# Camera_IR.net
KiCad netlist of a schematic drawn in EasyEDA
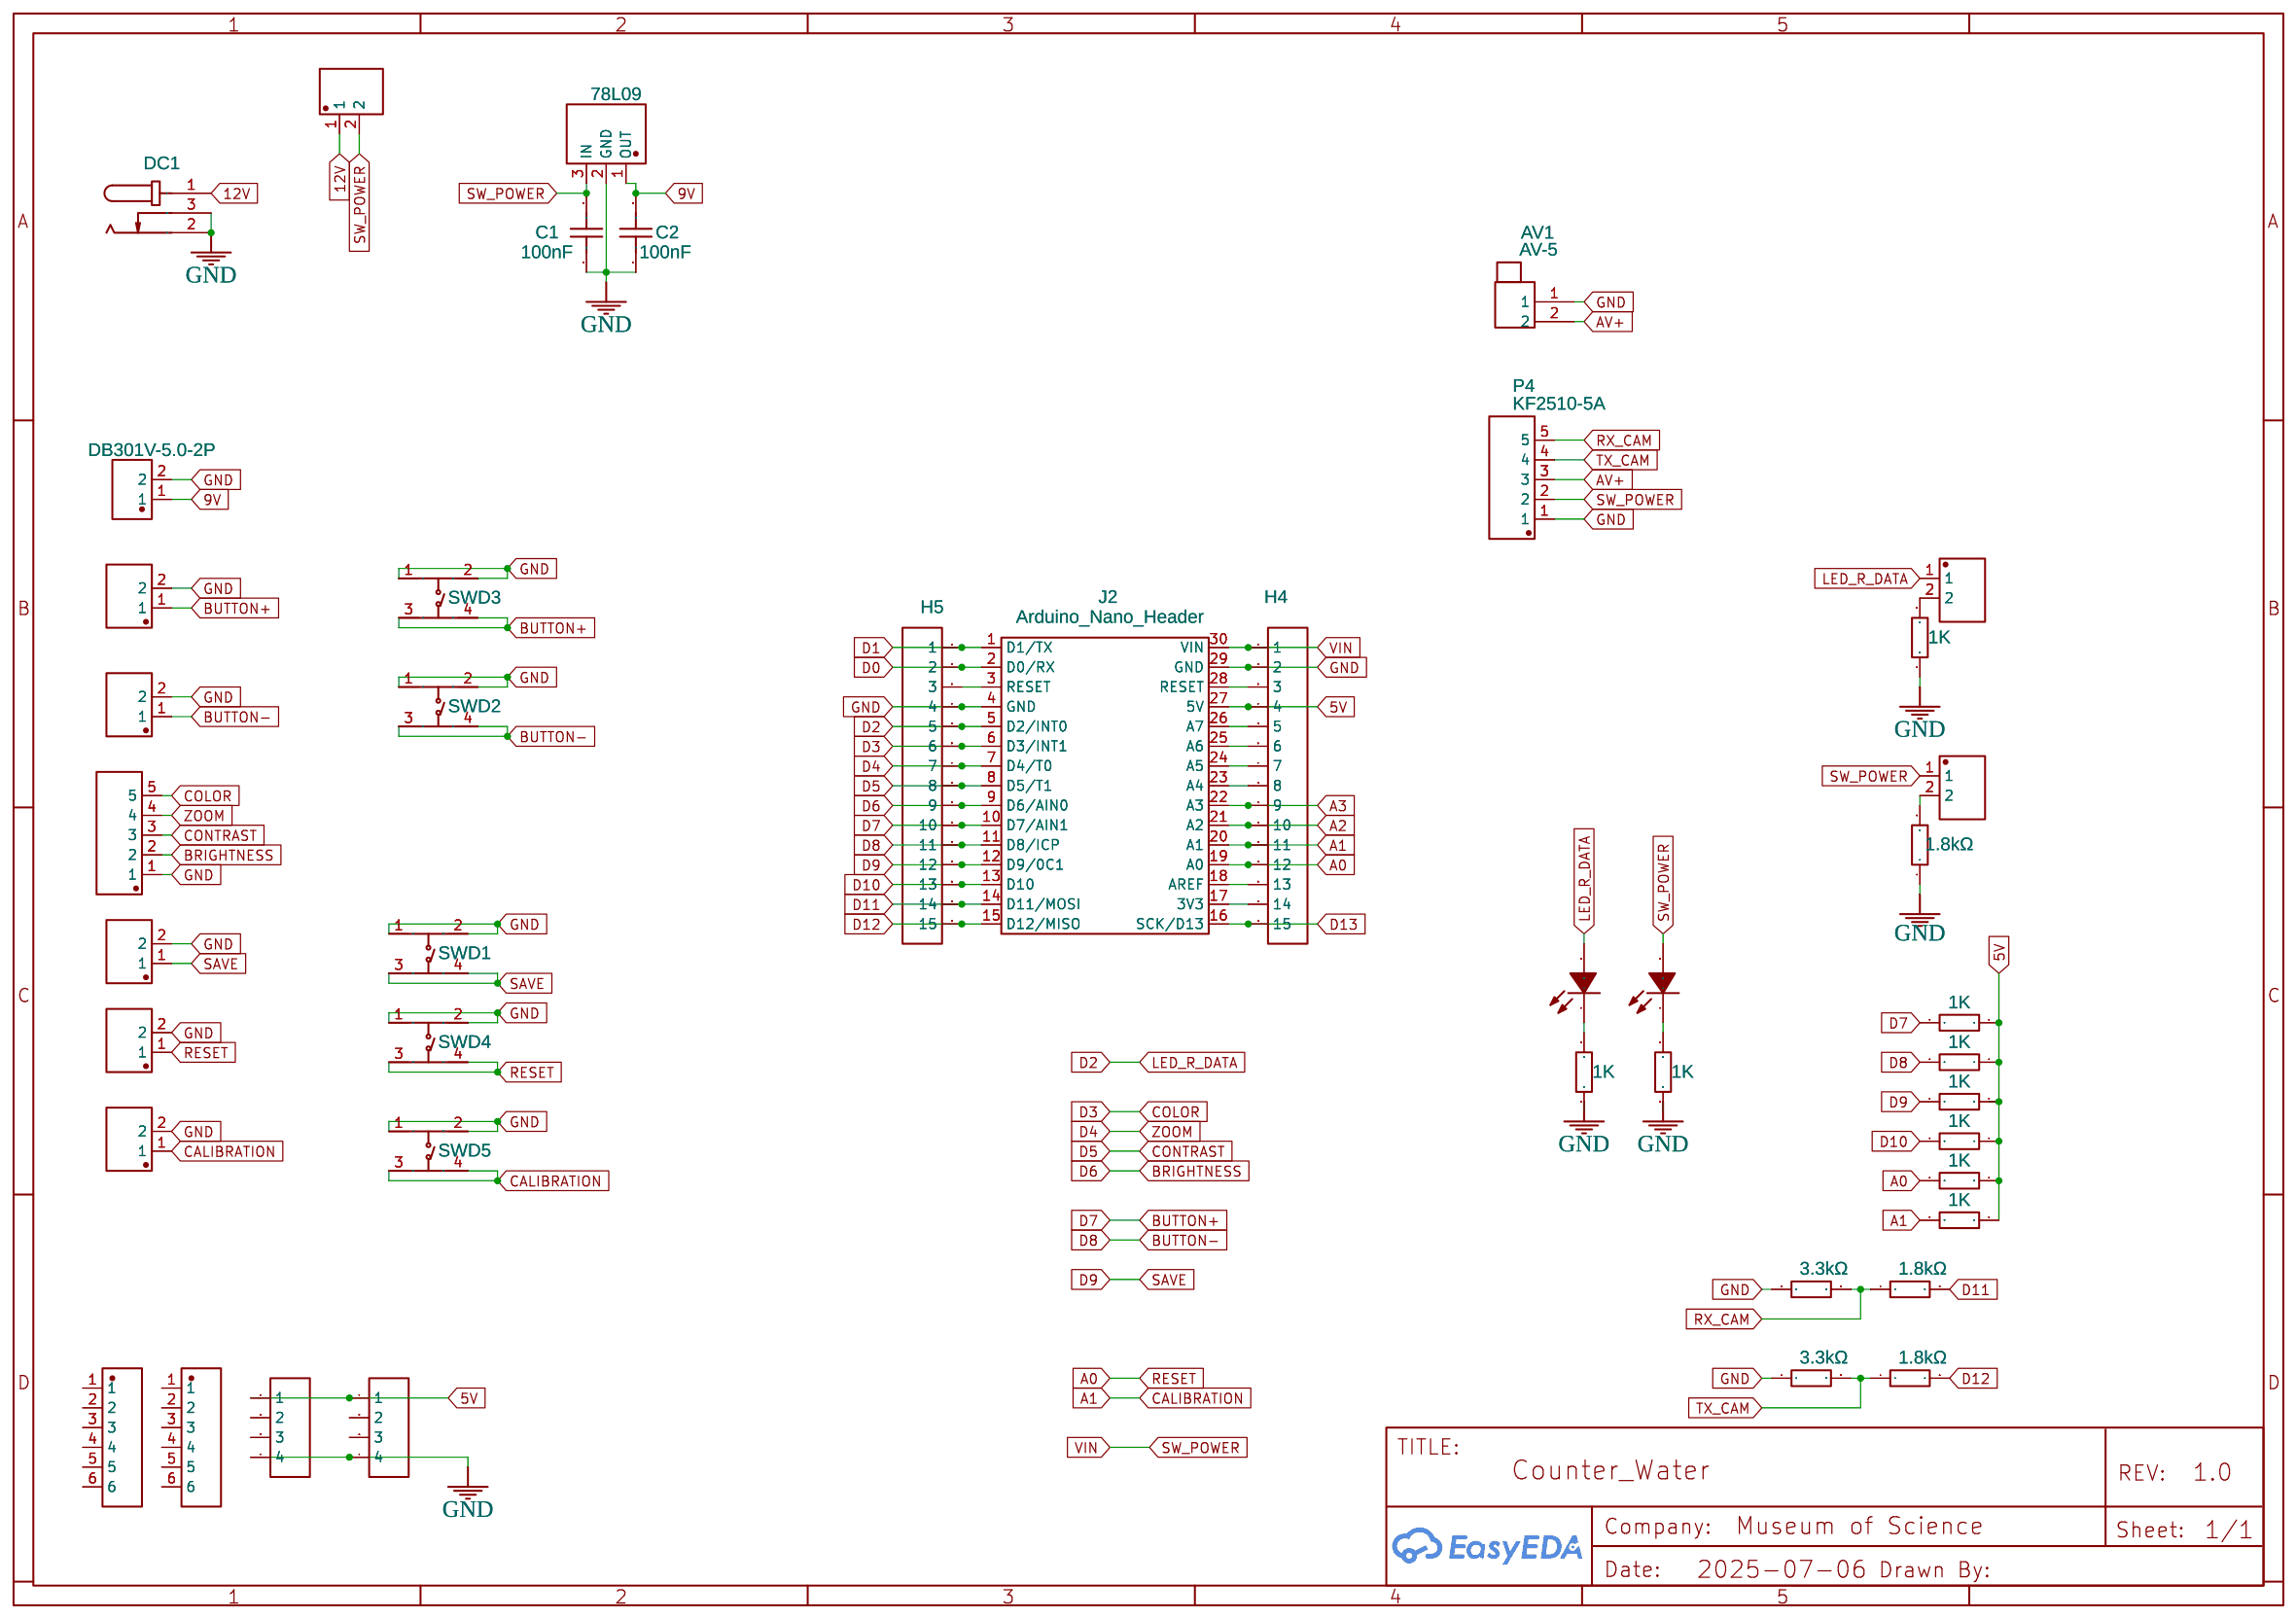
[diagram p0: schematic sheet]

(export (version "E")
  (design (tool "Eeschema 10.0.6"))
  (components
    (comp (ref "A0")
      (value "RESET")
      (fields (field (name "Manufacturer Part") "KF2510-2A") (field (name "Manufacturer") "BOOMELE"))
      (libsource (lib "") (part "KF2510-2A_1"))
    )
    (comp (ref "A1")
      (value "FFC")
      (fields (field (name "Manufacturer Part") "KF2510-2A") (field (name "Manufacturer") "BOOMELE"))
      (libsource (lib "") (part "KF2510-2A_1"))
    )
    (comp (ref "AV1")
      (value "AV-5")
      (fields (field (name "Manufacturer") "BOOMELE(博穆精密)"))
      (libsource (lib "") (part "AV-5"))
    )
    (comp (ref "C1")
      (value "100nF")
      (fields
        (field (name "Manufacturer Part") "CC0603KRX7R9BB104")
        (field (name "Manufacturer") "YAGEO(国巨)")
      )
      (libsource (lib "") (part "CC0603KRX7R9BB104"))
    )
    (comp (ref "C2")
      (value "100nF")
      (fields
        (field (name "Manufacturer Part") "CC0603KRX7R9BB104")
        (field (name "Manufacturer") "YAGEO(国巨)")
      )
      (libsource (lib "") (part "CC0603KRX7R9BB104"))
    )
    (comp (ref "D2")
      (value "LED")
      (fields (field (name "Manufacturer Part") "KF2510-2A") (field (name "Manufacturer") "BOOMELE"))
      (libsource (lib "") (part "KF2510-2A_3"))
    )
    (comp (ref "D7")
      (value "B+")
      (fields (field (name "Manufacturer Part") "KF2510-2A") (field (name "Manufacturer") "BOOMELE"))
      (libsource (lib "") (part "KF2510-2A"))
    )
    (comp (ref "D8")
      (value "B-")
      (fields (field (name "Manufacturer Part") "KF2510-2A") (field (name "Manufacturer") "BOOMELE"))
      (libsource (lib "") (part "KF2510-2A"))
    )
    (comp (ref "D9")
      (value "SAVE")
      (fields (field (name "Manufacturer Part") "KF2510-2A") (field (name "Manufacturer") "BOOMELE"))
      (libsource (lib "") (part "KF2510-2A"))
    )
    (comp (ref "DC1")
      (value "DC")
      (fields (field (name "Manufacturer Part") "DC005-2.0MM") (field (name "Manufacturer") "SOFNG"))
      (libsource (lib "") (part "DC005-2.0MM"))
    )
    (comp (ref "ERL1")
      (value "1K")
      (fields (field (name "Manufacturer Part") "0603WAF1001T5E") (field (name "Manufacturer") "UniOhm"))
      (libsource (lib "") (part "0603WAF1001T5E_1"))
    )
    (comp (ref "ERL2")
      (value "1K")
      (fields (field (name "Manufacturer Part") "0603WAF1001T5E") (field (name "Manufacturer") "UniOhm"))
      (libsource (lib "") (part "0603WAF1001T5E"))
    )
    (comp (ref "ERL3")
      (value "1K")
      (fields (field (name "Manufacturer Part") "0603WAF1001T5E") (field (name "Manufacturer") "UniOhm"))
      (libsource (lib "") (part "0603WAF1001T5E"))
    )
    (comp (ref "ERL4")
      (value "1K")
      (fields (field (name "Manufacturer Part") "0603WAF1001T5E") (field (name "Manufacturer") "UniOhm"))
      (libsource (lib "") (part "0603WAF1001T5E_1"))
    )
    (comp (ref "ERL5")
      (value "1K")
      (fields (field (name "Manufacturer Part") "0603WAF1001T5E") (field (name "Manufacturer") "UniOhm"))
      (libsource (lib "") (part "0603WAF1001T5E_1"))
    )
    (comp (ref "ERL6")
      (value "1K")
      (fields (field (name "Manufacturer Part") "0603WAF1001T5E") (field (name "Manufacturer") "UniOhm"))
      (libsource (lib "") (part "0603WAF1001T5E"))
    )
    (comp (ref "ERL9")
      (value "1K")
      (fields (field (name "Manufacturer Part") "0603WAF1001T5E") (field (name "Manufacturer") "UniOhm"))
      (libsource (lib "") (part "0603WAF1001T5E"))
    )
    (comp (ref "ERL11")
      (value "1K")
      (fields (field (name "Manufacturer Part") "0603WAF1001T5E") (field (name "Manufacturer") "UniOhm"))
      (libsource (lib "") (part "0603WAF1001T5E"))
    )
    (comp (ref "ERL12")
      (value "1K")
      (fields (field (name "Manufacturer Part") "0603WAF1001T5E") (field (name "Manufacturer") "UniOhm"))
      (libsource (lib "") (part "0603WAF1001T5E"))
    )
    (comp (ref "H4") (value "HDR-F-2.54_1x15") (libsource (lib "") (part "HDR-F-2.54_1x15")))
    (comp (ref "H5") (value "HDR-F-2.54_1x15") (libsource (lib "") (part "HDR-F-2.54_1x15_1")))
    (comp (ref "J2") (value "Arduino_Nano_Header") (libsource (lib "") (part "Arduino_Nano_Header")))
    (comp (ref "J6") (value "HDR-M-2.54_1x4") (libsource (lib "") (part "HDR-M-2.54_1x4")))
    (comp (ref "J7") (value "HDR-M-2.54_1x4") (libsource (lib "") (part "HDR-M-2.54_1x4")))
    (comp (ref "LED4")
      (value "KT-0603R")
      (fields (field (name "Manufacturer") "KENTO"))
      (libsource (lib "") (part "KT-0603R"))
    )
    (comp (ref "LED5")
      (value "KT-0603R")
      (fields (field (name "Manufacturer") "KENTO"))
      (libsource (lib "") (part "KT-0603R"))
    )
    (comp (ref "LED_P")
      (value "LED_POWER")
      (fields (field (name "Manufacturer Part") "KF2510-2A") (field (name "Manufacturer") "BOOMELE"))
      (libsource (lib "") (part "KF2510-2A_4"))
    )
    (comp (ref "P1")
      (value "KF2510-5A")
      (fields (field (name "Manufacturer Part") "2510-5A") (field (name "Manufacturer") "BOOMELE(博穆精密)"))
      (libsource (lib "") (part "KF2510-5A"))
    )
    (comp (ref "P2")
      (value "H6")
      (fields (field (name "Manufacturer Part") "2.54-1*6P母") (field (name "Manufacturer") "BOOMELE(博穆精密)"))
      (libsource (lib "") (part "Header-Female-2.54_1x6"))
    )
    (comp (ref "P3")
      (value "H6")
      (fields (field (name "Manufacturer Part") "2.54-1*6P母") (field (name "Manufacturer") "BOOMELE(博穆精密)"))
      (libsource (lib "") (part "Header-Female-2.54_1x6"))
    )
    (comp (ref "P4")
      (value "KF2510-5A")
      (fields (field (name "Manufacturer Part") "2510-5A") (field (name "Manufacturer") "BOOMELE(博穆精密)"))
      (libsource (lib "") (part "KF2510-5A"))
    )
    (comp (ref "R1")
      (value "1.8kΩ")
      (fields
        (field (name "Manufacturer Part") "0603WAF1801T5E")
        (field (name "Manufacturer") "UNI-ROYAL(厚声)")
      )
      (libsource (lib "") (part "0603WAF1801T5E"))
    )
    (comp (ref "R2")
      (value "1.8kΩ")
      (fields
        (field (name "Manufacturer Part") "0603WAF1801T5E")
        (field (name "Manufacturer") "UNI-ROYAL(厚声)")
      )
      (libsource (lib "") (part "0603WAF1801T5E"))
    )
    (comp (ref "R3")
      (value "3.3kΩ")
      (fields
        (field (name "Manufacturer Part") "0402WGF3301TCE")
        (field (name "Manufacturer") "UNI-ROYAL(厚声)")
      )
      (libsource (lib "") (part "0402WGF3301TCE"))
    )
    (comp (ref "R4")
      (value "3.3kΩ")
      (fields
        (field (name "Manufacturer Part") "0402WGF3301TCE")
        (field (name "Manufacturer") "UNI-ROYAL(厚声)")
      )
      (libsource (lib "") (part "0402WGF3301TCE"))
    )
    (comp (ref "R5")
      (value "1.8kΩ")
      (fields
        (field (name "Manufacturer Part") "0603WAF1801T5E")
        (field (name "Manufacturer") "UNI-ROYAL(厚声)")
      )
      (libsource (lib "") (part "0603WAF1801T5E_1"))
    )
    (comp (ref "SWD1")
      (value "TC-6610-7-160G")
      (fields (field (name "Manufacturer") "HCTL(华灿天禄)"))
      (libsource (lib "") (part "TC-6610-7-160G"))
    )
    (comp (ref "SWD2")
      (value "TC-6610-7-160G")
      (fields (field (name "Manufacturer") "HCTL(华灿天禄)"))
      (libsource (lib "") (part "TC-6610-7-160G"))
    )
    (comp (ref "SWD3")
      (value "TC-6610-7-160G")
      (fields (field (name "Manufacturer") "HCTL(华灿天禄)"))
      (libsource (lib "") (part "TC-6610-7-160G"))
    )
    (comp (ref "SWD4")
      (value "TC-6610-7-160G")
      (fields (field (name "Manufacturer") "HCTL(华灿天禄)"))
      (libsource (lib "") (part "TC-6610-7-160G"))
    )
    (comp (ref "SWD5")
      (value "TC-6610-7-160G")
      (fields (field (name "Manufacturer") "HCTL(华灿天禄)"))
      (libsource (lib "") (part "TC-6610-7-160G"))
    )
    (comp (ref "SW_P")
      (value "SW_P")
      (fields (field (name "Manufacturer Part") "KF2510-2A") (field (name "Manufacturer") "BOOMELE"))
      (libsource (lib "") (part "KF2510-2A_2"))
    )
    (comp (ref "U1")
      (value "78L09")
      (fields (field (name "Manufacturer") "CBI(创基)"))
      (libsource (lib "") (part "78L09U 78L09"))
    )
    (comp (ref "U3")
      (value "DB301V-5.0-2P")
      (fields
        (field (name "Manufacturer Part") "DB301V-5.0-2P-BU-S")
        (field (name "Manufacturer") "DORABO(地博电气)")
      )
      (libsource (lib "") (part "DB301V-5.0-2P"))
    )
  )
  (nets
    (net (code "1") (name "5V") (class "Default")
      (node (ref "ERL11") (pin "1") (pinfunction "1_1") (pintype "input"))
      (node (ref "ERL12") (pin "1") (pinfunction "1_1") (pintype "input"))
      (node (ref "ERL2") (pin "1") (pinfunction "1_1") (pintype "input"))
      (node (ref "ERL3") (pin "1") (pinfunction "1_1") (pintype "input"))
      (node (ref "ERL6") (pin "1") (pinfunction "1_1") (pintype "input"))
      (node (ref "ERL9") (pin "1") (pinfunction "1_1") (pintype "input"))
      (node (ref "H4") (pin "4") (pinfunction "4_4") (pintype "unspecified"))
      (node (ref "J2") (pin "27") (pinfunction "5V_27") (pintype "unspecified"))
      (node (ref "J6") (pin "1") (pinfunction "1_1") (pintype "unspecified"))
      (node (ref "J7") (pin "1") (pinfunction "1_1") (pintype "unspecified"))
    )
    (net (code "2") (name "9V") (class "Default")
      (node (ref "C2") (pin "2") (pinfunction "2_2") (pintype "unspecified"))
      (node (ref "U1") (pin "1") (pinfunction "OUT_1") (pintype "unspecified"))
      (node (ref "U3") (pin "1") (pinfunction "1_1") (pintype "unspecified"))
    )
    (net (code "3") (name "12V") (class "Default")
      (node (ref "DC1") (pin "1") (pinfunction "1_1") (pintype "unspecified"))
      (node (ref "SW_P") (pin "1") (pinfunction "1_1") (pintype "unspecified"))
    )
    (net (code "4") (name "A0") (class "Default")
      (node (ref "A0") (pin "1") (pinfunction "1_1") (pintype "unspecified"))
      (node (ref "ERL2") (pin "2") (pinfunction "2_2") (pintype "input"))
      (node (ref "H4") (pin "12") (pinfunction "12_12") (pintype "unspecified"))
      (node (ref "J2") (pin "19") (pinfunction "A0_19") (pintype "unspecified"))
      (node (ref "SWD4") (pin "3") (pinfunction "3_3") (pintype "unspecified"))
      (node (ref "SWD4") (pin "4") (pinfunction "4_4") (pintype "unspecified"))
    )
    (net (code "5") (name "A1") (class "Default")
      (node (ref "A1") (pin "1") (pinfunction "1_1") (pintype "unspecified"))
      (node (ref "ERL3") (pin "2") (pinfunction "2_2") (pintype "input"))
      (node (ref "H4") (pin "11") (pinfunction "11_11") (pintype "unspecified"))
      (node (ref "J2") (pin "20") (pinfunction "A1_20") (pintype "unspecified"))
      (node (ref "SWD5") (pin "3") (pinfunction "3_3") (pintype "unspecified"))
      (node (ref "SWD5") (pin "4") (pinfunction "4_4") (pintype "unspecified"))
    )
    (net (code "6") (name "A2") (class "Default")
      (node (ref "H4") (pin "10") (pinfunction "10_10") (pintype "unspecified"))
      (node (ref "J2") (pin "21") (pinfunction "A2_21") (pintype "unspecified"))
    )
    (net (code "7") (name "A3") (class "Default")
      (node (ref "H4") (pin "9") (pinfunction "9_9") (pintype "unspecified"))
      (node (ref "J2") (pin "22") (pinfunction "A3_22") (pintype "unspecified"))
    )
    (net (code "8") (name "AV+") (class "Default")
      (node (ref "AV1") (pin "2") (pinfunction "2_2") (pintype "unspecified"))
      (node (ref "P4") (pin "3") (pinfunction "3_3") (pintype "unspecified"))
    )
    (net (code "9") (name "BRIGHTNESS") (class "Default")
      (node (ref "H5") (pin "9") (pinfunction "9_9") (pintype "unspecified"))
      (node (ref "J2") (pin "9") (pinfunction "D6/AIN0_9") (pintype "unspecified"))
      (node (ref "P1") (pin "2") (pinfunction "2_2") (pintype "unspecified"))
    )
    (net (code "10") (name "BUTTON+") (class "Default")
      (node (ref "D7") (pin "1") (pinfunction "1_1") (pintype "unspecified"))
      (node (ref "ERL6") (pin "2") (pinfunction "2_2") (pintype "input"))
      (node (ref "H5") (pin "10") (pinfunction "10_10") (pintype "unspecified"))
      (node (ref "J2") (pin "10") (pinfunction "D7/AIN1_10") (pintype "unspecified"))
      (node (ref "SWD3") (pin "3") (pinfunction "3_3") (pintype "unspecified"))
      (node (ref "SWD3") (pin "4") (pinfunction "4_4") (pintype "unspecified"))
    )
    (net (code "11") (name "BUTTON-") (class "Default")
      (node (ref "D8") (pin "1") (pinfunction "1_1") (pintype "unspecified"))
      (node (ref "ERL11") (pin "2") (pinfunction "2_2") (pintype "input"))
      (node (ref "H5") (pin "11") (pinfunction "11_11") (pintype "unspecified"))
      (node (ref "J2") (pin "11") (pinfunction "D8/ICP_11") (pintype "unspecified"))
      (node (ref "SWD2") (pin "3") (pinfunction "3_3") (pintype "unspecified"))
      (node (ref "SWD2") (pin "4") (pinfunction "4_4") (pintype "unspecified"))
    )
    (net (code "12") (name "COLOR") (class "Default")
      (node (ref "H5") (pin "6") (pinfunction "6_6") (pintype "unspecified"))
      (node (ref "J2") (pin "6") (pinfunction "D3/INT1_6") (pintype "unspecified"))
      (node (ref "P1") (pin "5") (pinfunction "5_5") (pintype "unspecified"))
    )
    (net (code "13") (name "CONTRAST") (class "Default")
      (node (ref "H5") (pin "8") (pinfunction "8_8") (pintype "unspecified"))
      (node (ref "J2") (pin "8") (pinfunction "D5/T1_8") (pintype "unspecified"))
      (node (ref "P1") (pin "3") (pinfunction "3_3") (pintype "unspecified"))
    )
    (net (code "14") (name "D0") (class "Default")
      (node (ref "H5") (pin "2") (pinfunction "2_2") (pintype "unspecified"))
      (node (ref "J2") (pin "2") (pinfunction "D0/RX_2") (pintype "unspecified"))
    )
    (net (code "15") (name "D1") (class "Default")
      (node (ref "H5") (pin "1") (pinfunction "1_1") (pintype "unspecified"))
      (node (ref "J2") (pin "1") (pinfunction "D1/TX_1") (pintype "unspecified"))
    )
    (net (code "16") (name "D2") (class "Default")
      (node (ref "D2") (pin "1") (pinfunction "1_1") (pintype "unspecified"))
      (node (ref "H5") (pin "5") (pinfunction "5_5") (pintype "unspecified"))
      (node (ref "J2") (pin "5") (pinfunction "D2/INT0_5") (pintype "unspecified"))
      (node (ref "LED5") (pin "2") (pinfunction "A_2") (pintype "unspecified"))
    )
    (net (code "17") (name "D4") (class "Default")
      (node (ref "H5") (pin "7") (pinfunction "7_7") (pintype "unspecified"))
      (node (ref "J2") (pin "7") (pinfunction "D4/T0_7") (pintype "unspecified"))
      (node (ref "P1") (pin "4") (pinfunction "4_4") (pintype "unspecified"))
    )
    (net (code "18") (name "D9") (class "Default")
      (node (ref "D9") (pin "1") (pinfunction "1_1") (pintype "unspecified"))
      (node (ref "ERL9") (pin "2") (pinfunction "2_2") (pintype "input"))
      (node (ref "H5") (pin "12") (pinfunction "12_12") (pintype "unspecified"))
      (node (ref "J2") (pin "12") (pinfunction "D9/0C1_12") (pintype "unspecified"))
      (node (ref "SWD1") (pin "3") (pinfunction "3_3") (pintype "unspecified"))
      (node (ref "SWD1") (pin "4") (pinfunction "4_4") (pintype "unspecified"))
    )
    (net (code "19") (name "D10") (class "Default")
      (node (ref "ERL12") (pin "2") (pinfunction "2_2") (pintype "input"))
      (node (ref "H5") (pin "13") (pinfunction "13_13") (pintype "unspecified"))
      (node (ref "J2") (pin "13") (pinfunction "D10_13") (pintype "unspecified"))
    )
    (net (code "20") (name "D11") (class "Default")
      (node (ref "H5") (pin "14") (pinfunction "14_14") (pintype "unspecified"))
      (node (ref "J2") (pin "14") (pinfunction "D11/MOSI_14") (pintype "unspecified"))
      (node (ref "R1") (pin "2") (pinfunction "2_2") (pintype "input"))
    )
    (net (code "21") (name "D12") (class "Default")
      (node (ref "H5") (pin "15") (pinfunction "15_15") (pintype "unspecified"))
      (node (ref "J2") (pin "15") (pinfunction "D12/MISO_15") (pintype "unspecified"))
      (node (ref "R2") (pin "2") (pinfunction "2_2") (pintype "input"))
    )
    (net (code "22") (name "D13") (class "Default")
      (node (ref "H4") (pin "15") (pinfunction "15_15") (pintype "unspecified"))
      (node (ref "J2") (pin "16") (pinfunction "SCK/D13_16") (pintype "unspecified"))
    )
    (net (code "23") (name "GND") (class "Default")
      (node (ref "A0") (pin "2") (pinfunction "2_2") (pintype "unspecified"))
      (node (ref "A1") (pin "2") (pinfunction "2_2") (pintype "unspecified"))
      (node (ref "AV1") (pin "1") (pinfunction "1_1") (pintype "unspecified"))
      (node (ref "C1") (pin "1") (pinfunction "1_1") (pintype "unspecified"))
      (node (ref "C2") (pin "1") (pinfunction "1_1") (pintype "unspecified"))
      (node (ref "D7") (pin "2") (pinfunction "2_2") (pintype "unspecified"))
      (node (ref "D8") (pin "2") (pinfunction "2_2") (pintype "unspecified"))
      (node (ref "D9") (pin "2") (pinfunction "2_2") (pintype "unspecified"))
      (node (ref "DC1") (pin "2") (pinfunction "2_2") (pintype "unspecified"))
      (node (ref "DC1") (pin "3") (pinfunction "3_3") (pintype "unspecified"))
      (node (ref "ERL1") (pin "1") (pinfunction "1_1") (pintype "input"))
      (node (ref "ERL4") (pin "1") (pinfunction "1_1") (pintype "input"))
      (node (ref "ERL5") (pin "1") (pinfunction "1_1") (pintype "input"))
      (node (ref "H4") (pin "2") (pinfunction "2_2") (pintype "unspecified"))
      (node (ref "H5") (pin "4") (pinfunction "4_4") (pintype "unspecified"))
      (node (ref "J2") (pin "29") (pinfunction "GND_29") (pintype "unspecified"))
      (node (ref "J2") (pin "4") (pinfunction "GND_4") (pintype "unspecified"))
      (node (ref "J6") (pin "4") (pinfunction "4_4") (pintype "unspecified"))
      (node (ref "J7") (pin "4") (pinfunction "4_4") (pintype "unspecified"))
      (node (ref "P1") (pin "1") (pinfunction "1_1") (pintype "unspecified"))
      (node (ref "P4") (pin "1") (pinfunction "1_1") (pintype "unspecified"))
      (node (ref "R3") (pin "1") (pinfunction "1_1") (pintype "input"))
      (node (ref "R4") (pin "1") (pinfunction "1_1") (pintype "input"))
      (node (ref "R5") (pin "1") (pinfunction "1_1") (pintype "input"))
      (node (ref "SWD1") (pin "1") (pinfunction "1_1") (pintype "unspecified"))
      (node (ref "SWD1") (pin "2") (pinfunction "2_2") (pintype "unspecified"))
      (node (ref "SWD2") (pin "1") (pinfunction "1_1") (pintype "unspecified"))
      (node (ref "SWD2") (pin "2") (pinfunction "2_2") (pintype "unspecified"))
      (node (ref "SWD3") (pin "1") (pinfunction "1_1") (pintype "unspecified"))
      (node (ref "SWD3") (pin "2") (pinfunction "2_2") (pintype "unspecified"))
      (node (ref "SWD4") (pin "1") (pinfunction "1_1") (pintype "unspecified"))
      (node (ref "SWD4") (pin "2") (pinfunction "2_2") (pintype "unspecified"))
      (node (ref "SWD5") (pin "1") (pinfunction "1_1") (pintype "unspecified"))
      (node (ref "SWD5") (pin "2") (pinfunction "2_2") (pintype "unspecified"))
      (node (ref "U1") (pin "2") (pinfunction "GND_2") (pintype "unspecified"))
      (node (ref "U3") (pin "2") (pinfunction "2_2") (pintype "unspecified"))
    )
    (net (code "24") (name "Net-(D2-Pad2)") (class "Default")
      (node (ref "D2") (pin "2") (pinfunction "2_2") (pintype "unspecified"))
      (node (ref "ERL5") (pin "2") (pinfunction "2_2") (pintype "input"))
    )
    (net (code "25") (name "Net-(H4-Pad3)") (class "Default")
      (node (ref "H4") (pin "3") (pinfunction "3_3") (pintype "unspecified"))
      (node (ref "J2") (pin "28") (pinfunction "RESET_28") (pintype "unspecified"))
    )
    (net (code "26") (name "Net-(H5-Pad3)") (class "Default")
      (node (ref "H5") (pin "3") (pinfunction "3_3") (pintype "unspecified"))
      (node (ref "J2") (pin "3") (pinfunction "RESET_3") (pintype "unspecified"))
    )
    (net (code "27") (name "Net-(J2-3V3)") (class "Default")
      (node (ref "H4") (pin "14") (pinfunction "14_14") (pintype "unspecified"))
      (node (ref "J2") (pin "17") (pinfunction "3V3_17") (pintype "unspecified"))
    )
    (net (code "28") (name "Net-(J2-A4)") (class "Default")
      (node (ref "H4") (pin "8") (pinfunction "8_8") (pintype "unspecified"))
      (node (ref "J2") (pin "23") (pinfunction "A4_23") (pintype "unspecified"))
    )
    (net (code "29") (name "Net-(J2-A5)") (class "Default")
      (node (ref "H4") (pin "7") (pinfunction "7_7") (pintype "unspecified"))
      (node (ref "J2") (pin "24") (pinfunction "A5_24") (pintype "unspecified"))
    )
    (net (code "30") (name "Net-(J2-A6)") (class "Default")
      (node (ref "H4") (pin "6") (pinfunction "6_6") (pintype "unspecified"))
      (node (ref "J2") (pin "25") (pinfunction "A6_25") (pintype "unspecified"))
    )
    (net (code "31") (name "Net-(J2-A7)") (class "Default")
      (node (ref "H4") (pin "5") (pinfunction "5_5") (pintype "unspecified"))
      (node (ref "J2") (pin "26") (pinfunction "A7_26") (pintype "unspecified"))
    )
    (net (code "32") (name "Net-(J2-AREF)") (class "Default")
      (node (ref "H4") (pin "13") (pinfunction "13_13") (pintype "unspecified"))
      (node (ref "J2") (pin "18") (pinfunction "AREF_18") (pintype "unspecified"))
    )
    (net (code "33") (name "Net-(LED4-K)") (class "Default")
      (node (ref "ERL4") (pin "2") (pinfunction "2_2") (pintype "input"))
      (node (ref "LED4") (pin "1") (pinfunction "K_1") (pintype "unspecified"))
    )
    (net (code "34") (name "Net-(LED5-K)") (class "Default")
      (node (ref "ERL1") (pin "2") (pinfunction "2_2") (pintype "input"))
      (node (ref "LED5") (pin "1") (pinfunction "K_1") (pintype "unspecified"))
    )
    (net (code "35") (name "Net-(LED_P-Pad2)") (class "Default")
      (node (ref "LED_P") (pin "2") (pinfunction "2_2") (pintype "unspecified"))
      (node (ref "R5") (pin "2") (pinfunction "2_2") (pintype "input"))
    )
    (net (code "36") (name "RX_CAM") (class "Default")
      (node (ref "P4") (pin "5") (pinfunction "5_5") (pintype "unspecified"))
      (node (ref "R1") (pin "1") (pinfunction "1_1") (pintype "input"))
      (node (ref "R3") (pin "2") (pinfunction "2_2") (pintype "input"))
    )
    (net (code "37") (name "SW_POWER") (class "Default")
      (node (ref "C1") (pin "2") (pinfunction "2_2") (pintype "unspecified"))
      (node (ref "H4") (pin "1") (pinfunction "1_1") (pintype "unspecified"))
      (node (ref "J2") (pin "30") (pinfunction "VIN_30") (pintype "unspecified"))
      (node (ref "LED4") (pin "2") (pinfunction "A_2") (pintype "unspecified"))
      (node (ref "LED_P") (pin "1") (pinfunction "1_1") (pintype "unspecified"))
      (node (ref "P4") (pin "2") (pinfunction "2_2") (pintype "unspecified"))
      (node (ref "SW_P") (pin "2") (pinfunction "2_2") (pintype "unspecified"))
      (node (ref "U1") (pin "3") (pinfunction "IN_3") (pintype "unspecified"))
    )
    (net (code "38") (name "TX_CAM") (class "Default")
      (node (ref "P4") (pin "4") (pinfunction "4_4") (pintype "unspecified"))
      (node (ref "R2") (pin "1") (pinfunction "1_1") (pintype "input"))
      (node (ref "R4") (pin "2") (pinfunction "2_2") (pintype "input"))
    )
    (net (code "39") (name "unconnected-(J6-Pad2)") (class "Default")
      (node (ref "J6") (pin "2") (pinfunction "2_2") (pintype "unspecified"))
    )
    (net (code "40") (name "unconnected-(J6-Pad3)") (class "Default")
      (node (ref "J6") (pin "3") (pinfunction "3_3") (pintype "unspecified"))
    )
    (net (code "41") (name "unconnected-(J7-Pad2)") (class "Default")
      (node (ref "J7") (pin "2") (pinfunction "2_2") (pintype "unspecified"))
    )
    (net (code "42") (name "unconnected-(J7-Pad3)") (class "Default")
      (node (ref "J7") (pin "3") (pinfunction "3_3") (pintype "unspecified"))
    )
    (net (code "43") (name "unconnected-(P2-Pad1)") (class "Default")
      (node (ref "P2") (pin "1") (pinfunction "1_1") (pintype "unspecified"))
    )
    (net (code "44") (name "unconnected-(P2-Pad2)") (class "Default")
      (node (ref "P2") (pin "2") (pinfunction "2_2") (pintype "unspecified"))
    )
    (net (code "45") (name "unconnected-(P2-Pad3)") (class "Default")
      (node (ref "P2") (pin "3") (pinfunction "3_3") (pintype "unspecified"))
    )
    (net (code "46") (name "unconnected-(P2-Pad4)") (class "Default")
      (node (ref "P2") (pin "4") (pinfunction "4_4") (pintype "unspecified"))
    )
    (net (code "47") (name "unconnected-(P2-Pad5)") (class "Default")
      (node (ref "P2") (pin "5") (pinfunction "5_5") (pintype "unspecified"))
    )
    (net (code "48") (name "unconnected-(P2-Pad6)") (class "Default")
      (node (ref "P2") (pin "6") (pinfunction "6_6") (pintype "unspecified"))
    )
    (net (code "49") (name "unconnected-(P3-Pad1)") (class "Default")
      (node (ref "P3") (pin "1") (pinfunction "1_1") (pintype "unspecified"))
    )
    (net (code "50") (name "unconnected-(P3-Pad2)") (class "Default")
      (node (ref "P3") (pin "2") (pinfunction "2_2") (pintype "unspecified"))
    )
    (net (code "51") (name "unconnected-(P3-Pad3)") (class "Default")
      (node (ref "P3") (pin "3") (pinfunction "3_3") (pintype "unspecified"))
    )
    (net (code "52") (name "unconnected-(P3-Pad4)") (class "Default")
      (node (ref "P3") (pin "4") (pinfunction "4_4") (pintype "unspecified"))
    )
    (net (code "53") (name "unconnected-(P3-Pad5)") (class "Default")
      (node (ref "P3") (pin "5") (pinfunction "5_5") (pintype "unspecified"))
    )
    (net (code "54") (name "unconnected-(P3-Pad6)") (class "Default")
      (node (ref "P3") (pin "6") (pinfunction "6_6") (pintype "unspecified"))
    )
  )
)
